# p0b-002.net
KiCad netlist of a schematic drawn in EAGLE
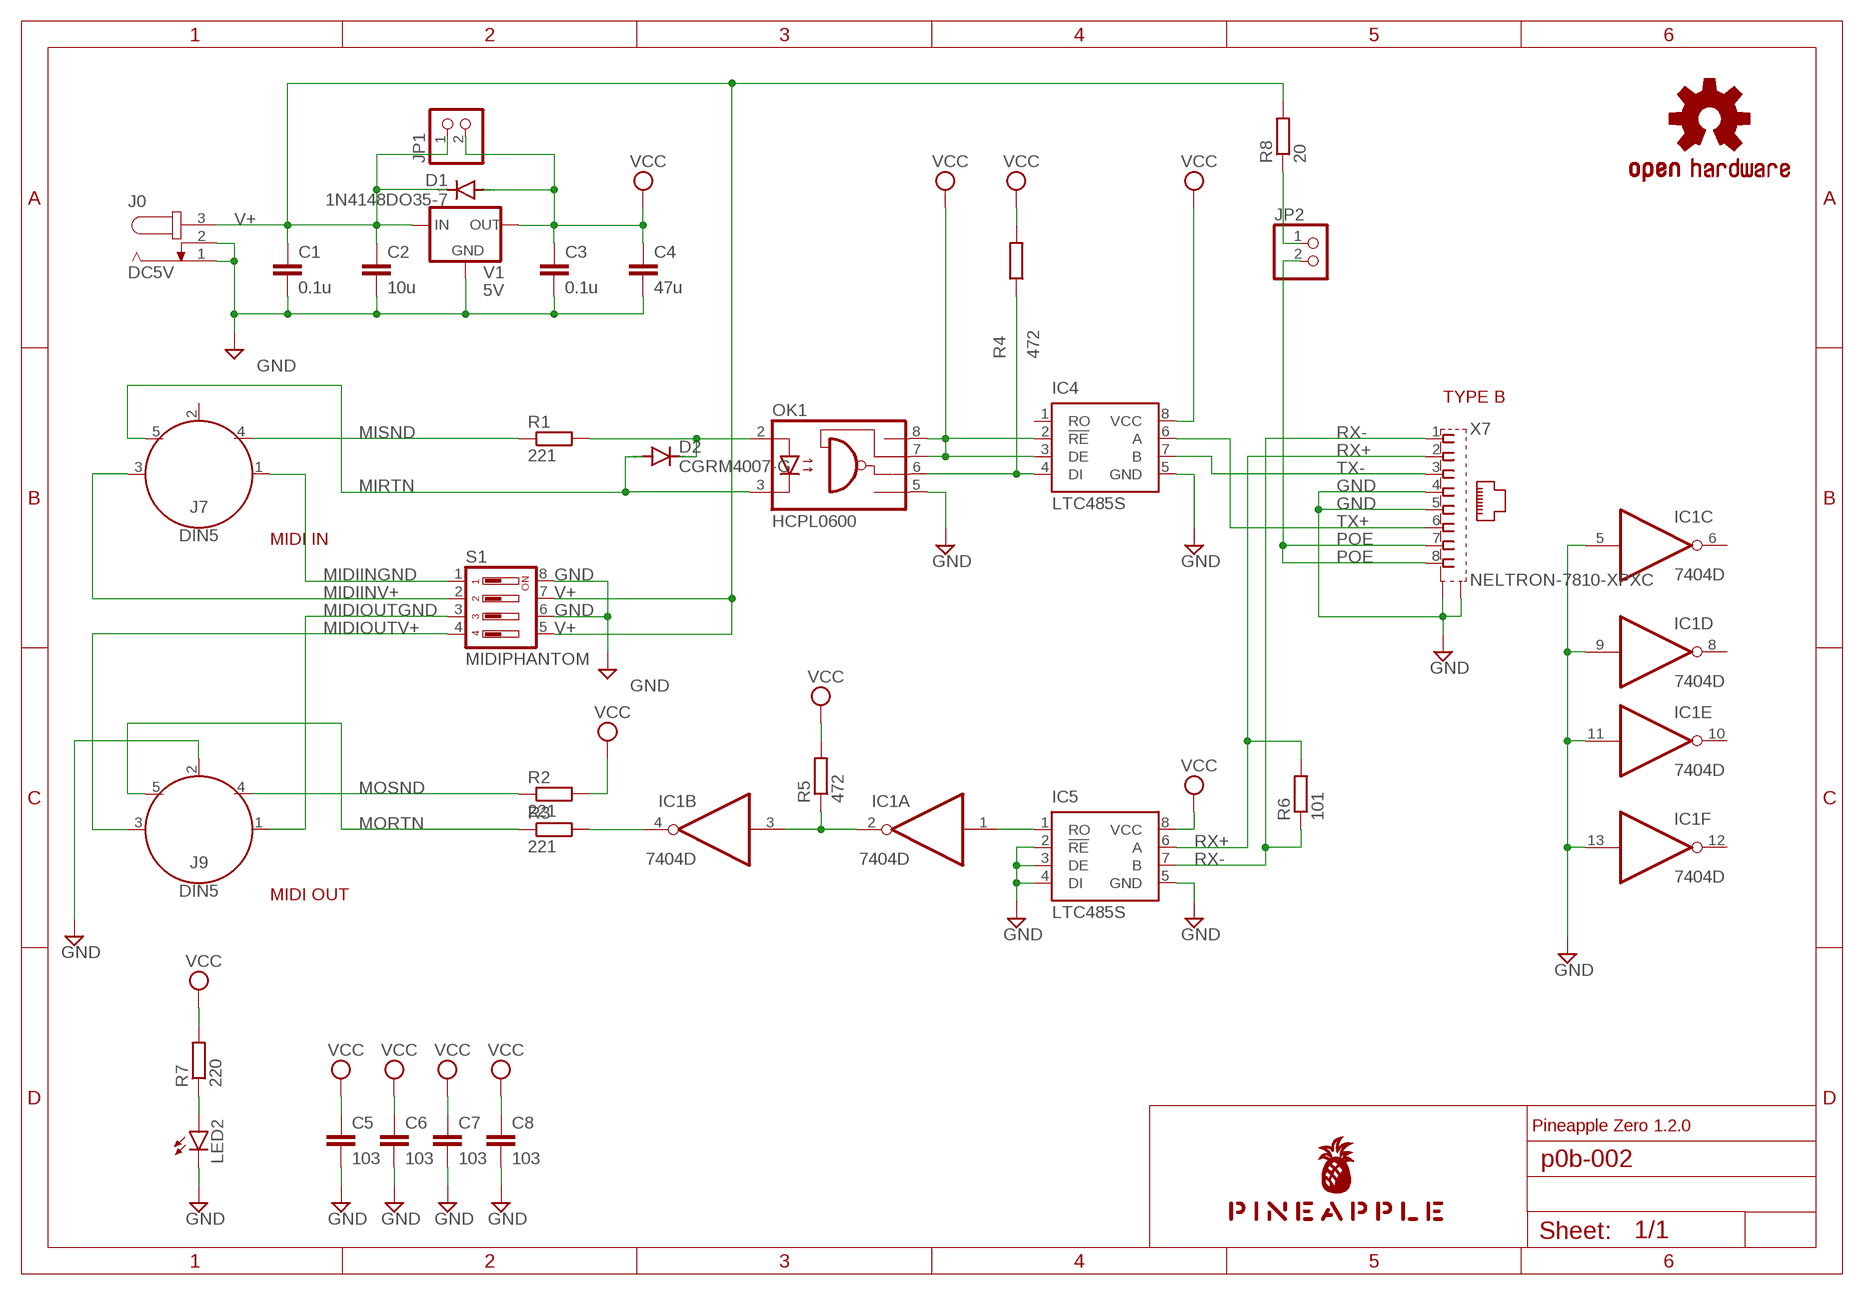
[diagram p0: schematic, sheet 1]

(export (version "E")
  (design (tool "Eeschema 10.0.6"))
  (components
    (comp (ref "C1")
      (value "0.1u")
      (footprint "eagle-import:C025-025X050")
      (libsource (lib "eagle-import") (part "C-EU025-025X050"))
    )
    (comp (ref "C2")
      (value "10u")
      (footprint "eagle-import:C025-030X050")
      (libsource (lib "eagle-import") (part "C-EU025-030X050"))
    )
    (comp (ref "C3")
      (value "0.1u")
      (footprint "eagle-import:C025-025X050")
      (libsource (lib "eagle-import") (part "C-EU025-025X050"))
    )
    (comp (ref "C4")
      (value "47u")
      (footprint "eagle-import:C025-050X050")
      (libsource (lib "eagle-import") (part "C-EU025-050X050"))
    )
    (comp (ref "C5")
      (value "103")
      (footprint "eagle-import:C1206")
      (libsource (lib "eagle-import") (part "C-EUC1206"))
    )
    (comp (ref "C6")
      (value "103")
      (footprint "eagle-import:C1206")
      (libsource (lib "eagle-import") (part "C-EUC1206"))
    )
    (comp (ref "C7")
      (value "103")
      (footprint "eagle-import:C1206")
      (libsource (lib "eagle-import") (part "C-EUC1206"))
    )
    (comp (ref "C8")
      (value "103")
      (footprint "eagle-import:C1206")
      (libsource (lib "eagle-import") (part "C-EUC1206"))
    )
    (comp (ref "D1")
      (value "1N4148DO35-7")
      (footprint "eagle-import:DO35-7")
      (libsource (lib "eagle-import") (part "1N4148DO35-7"))
    )
    (comp (ref "D2")
      (value "CGRM4007-G")
      (footprint "eagle-import:SOD-123_MINI-SMA")
      (libsource (lib "eagle-import") (part "CGRM400-G7"))
    )
    (comp (ref "IC1")
      (value "7404D")
      (footprint "eagle-import:SO14")
      (libsource (lib "eagle-import") (part "7404D"))
    )
    (comp (ref "IC4")
      (value "LTC485S")
      (footprint "eagle-import:SOIC8")
      (libsource (lib "eagle-import") (part "LTC485S"))
    )
    (comp (ref "IC5")
      (value "LTC485S")
      (footprint "eagle-import:SOIC8")
      (libsource (lib "eagle-import") (part "LTC485S"))
    )
    (comp (ref "J0")
      (value "DC5V")
      (footprint "eagle-import:SPC4077")
      (libsource (lib "eagle-import") (part "JACK-PLUG0"))
    )
    (comp (ref "J7")
      (value "DIN5")
      (footprint "eagle-import:DIN5-RA-PTH")
      (libsource (lib "eagle-import") (part "DIN5"))
    )
    (comp (ref "J9")
      (value "DIN5")
      (footprint "eagle-import:DIN5-RA-PTH")
      (libsource (lib "eagle-import") (part "DIN5"))
    )
    (comp (ref "JP1")
      (value "PINHD-1X2")
      (footprint "eagle-import:1X02")
      (libsource (lib "eagle-import") (part "PINHD-1X2"))
    )
    (comp (ref "JP2")
      (value "PINHD-1X2")
      (footprint "eagle-import:1X02")
      (libsource (lib "eagle-import") (part "PINHD-1X2"))
    )
    (comp (ref "LED2")
      (value "LEDCHIPLED_1206")
      (footprint "eagle-import:CHIPLED_1206")
      (libsource (lib "eagle-import") (part "LEDCHIPLED_1206"))
    )
    (comp (ref "LOGO1")
      (value "OSHW-LOGOS-COPPER")
      (footprint "eagle-import:OSHW-LOGO-S_COPPER")
      (libsource (lib "eagle-import") (part "OSHW-LOGOS-COPPER"))
    )
    (comp (ref "OK1")
      (value "HCPL0600")
      (footprint "eagle-import:SOIC08")
      (fields (field (name "MF") "AGILENT TECHNOLOGIES") (field (name "MPN") "HCPL-0600-000E"))
      (libsource (lib "eagle-import") (part "HCPL0600"))
    )
    (comp (ref "R1")
      (value "221")
      (footprint "eagle-import:M2012")
      (libsource (lib "eagle-import") (part "R-EU_M2012"))
    )
    (comp (ref "R2")
      (value "221")
      (footprint "eagle-import:M2012")
      (libsource (lib "eagle-import") (part "R-EU_M2012"))
    )
    (comp (ref "R3")
      (value "221")
      (footprint "eagle-import:M2012")
      (libsource (lib "eagle-import") (part "R-EU_M2012"))
    )
    (comp (ref "R4")
      (value "472")
      (footprint "eagle-import:M2012")
      (libsource (lib "eagle-import") (part "R-EU_M2012"))
    )
    (comp (ref "R5")
      (value "472")
      (footprint "eagle-import:M2012")
      (libsource (lib "eagle-import") (part "R-EU_M2012"))
    )
    (comp (ref "R6")
      (value "101")
      (footprint "eagle-import:M2012")
      (libsource (lib "eagle-import") (part "R-EU_M2012"))
    )
    (comp (ref "R7")
      (value "220")
      (footprint "eagle-import:M2012")
      (libsource (lib "eagle-import") (part "R-EU_M2012"))
    )
    (comp (ref "R8")
      (value "20")
      (footprint "eagle-import:M2012")
      (libsource (lib "eagle-import") (part "R-EU_M2012"))
    )
    (comp (ref "S1")
      (value "MIDIPHANTOM")
      (footprint "eagle-import:DIP04YL")
      (libsource (lib "eagle-import") (part "DIP04YL"))
    )
    (comp (ref "U$1")
      (value "PINEAPPLE450")
      (footprint "eagle-import:PINEAPPLE450")
      (libsource (lib "eagle-import") (part "PINEAPPLE450"))
    )
    (comp (ref "V1")
      (value "5V")
      (footprint "eagle-import:78XXS")
      (libsource (lib "eagle-import") (part "78XXS"))
    )
    (comp (ref "X7")
      (value "NELTRON-7810-XPXC")
      (footprint "eagle-import:NELTRON-7810-XPXC-FOOTPRINT")
      (libsource (lib "eagle-import") (part "NELTRON-7810-XPXC"))
    )
  )
  (nets
    (net (code "1") (name "/MIDIINGND") (class "Default")
      (node (ref "J7") (pin "1") (pinfunction "1_1") (pintype "bidirectional"))
      (node (ref "S1") (pin "1") (pinfunction "1_1") (pintype "passive"))
    )
    (net (code "2") (name "/MIDIINV+") (class "Default")
      (node (ref "J7") (pin "3") (pinfunction "3_3") (pintype "bidirectional"))
      (node (ref "S1") (pin "2") (pinfunction "2_2") (pintype "passive"))
    )
    (net (code "3") (name "/MIDIOUTGND") (class "Default")
      (node (ref "J9") (pin "1") (pinfunction "1_1") (pintype "bidirectional"))
      (node (ref "S1") (pin "3") (pinfunction "3_3") (pintype "passive"))
    )
    (net (code "4") (name "/MIDIOUTV+") (class "Default")
      (node (ref "J9") (pin "3") (pinfunction "3_3") (pintype "bidirectional"))
      (node (ref "S1") (pin "4") (pinfunction "4_4") (pintype "passive"))
    )
    (net (code "5") (name "/MIRTN") (class "Default")
      (node (ref "D2") (pin "A") (pinfunction "A_A") (pintype "passive"))
      (node (ref "J7") (pin "5") (pinfunction "5_5") (pintype "bidirectional"))
      (node (ref "OK1") (pin "3") (pinfunction "C_3") (pintype "passive"))
    )
    (net (code "6") (name "/MISND") (class "Default")
      (node (ref "J7") (pin "4") (pinfunction "4_4") (pintype "bidirectional"))
      (node (ref "R1") (pin "1") (pinfunction "1_1") (pintype "passive"))
    )
    (net (code "7") (name "/MORTN") (class "Default")
      (node (ref "J9") (pin "5") (pinfunction "5_5") (pintype "bidirectional"))
      (node (ref "R3") (pin "1") (pinfunction "1_1") (pintype "passive"))
    )
    (net (code "8") (name "/MOSND") (class "Default")
      (node (ref "J9") (pin "4") (pinfunction "4_4") (pintype "bidirectional"))
      (node (ref "R2") (pin "1") (pinfunction "1_1") (pintype "passive"))
    )
    (net (code "9") (name "/POE") (class "Default")
      (node (ref "JP2") (pin "2") (pinfunction "2_2") (pintype "passive"))
      (node (ref "X7") (pin "7") (pinfunction "7_7") (pintype "passive"))
      (node (ref "X7") (pin "8") (pinfunction "8_8") (pintype "passive"))
    )
    (net (code "10") (name "/RX+") (class "Default")
      (node (ref "IC5") (pin "6") (pinfunction "A_6") (pintype "bidirectional"))
      (node (ref "R6") (pin "2") (pinfunction "2_2") (pintype "passive"))
      (node (ref "X7") (pin "2") (pinfunction "2_2") (pintype "passive"))
    )
    (net (code "11") (name "/RX-") (class "Default")
      (node (ref "IC5") (pin "7") (pinfunction "B_7") (pintype "bidirectional"))
      (node (ref "R6") (pin "1") (pinfunction "1_1") (pintype "passive"))
      (node (ref "X7") (pin "1") (pinfunction "1_1") (pintype "passive"))
    )
    (net (code "12") (name "/TX+") (class "Default")
      (node (ref "IC4") (pin "6") (pinfunction "A_6") (pintype "bidirectional"))
      (node (ref "X7") (pin "6") (pinfunction "6_6") (pintype "passive"))
    )
    (net (code "13") (name "/TX-") (class "Default")
      (node (ref "IC4") (pin "7") (pinfunction "B_7") (pintype "bidirectional"))
      (node (ref "X7") (pin "3") (pinfunction "3_3") (pintype "passive"))
    )
    (net (code "14") (name "/V+") (class "Default")
      (node (ref "C1") (pin "1") (pinfunction "1_1") (pintype "passive"))
      (node (ref "C2") (pin "1") (pinfunction "1_1") (pintype "passive"))
      (node (ref "D1") (pin "C") (pinfunction "C_C") (pintype "passive"))
      (node (ref "J0") (pin "3") (pinfunction "3_3") (pintype "passive"))
      (node (ref "JP1") (pin "1") (pinfunction "1_1") (pintype "passive"))
      (node (ref "R8") (pin "2") (pinfunction "2_2") (pintype "passive"))
      (node (ref "S1") (pin "5") (pinfunction "5_5") (pintype "passive"))
      (node (ref "S1") (pin "7") (pinfunction "7_7") (pintype "passive"))
      (node (ref "V1") (pin "IN") (pinfunction "IN_IN") (pintype "input"))
    )
    (net (code "15") (name "GND") (class "Default")
      (node (ref "C1") (pin "2") (pinfunction "2_2") (pintype "passive"))
      (node (ref "C2") (pin "2") (pinfunction "2_2") (pintype "passive"))
      (node (ref "C3") (pin "2") (pinfunction "2_2") (pintype "passive"))
      (node (ref "C4") (pin "2") (pinfunction "2_2") (pintype "passive"))
      (node (ref "C5") (pin "2") (pinfunction "2_2") (pintype "passive"))
      (node (ref "C6") (pin "2") (pinfunction "2_2") (pintype "passive"))
      (node (ref "C7") (pin "2") (pinfunction "2_2") (pintype "passive"))
      (node (ref "C8") (pin "2") (pinfunction "2_2") (pintype "passive"))
      (node (ref "IC1") (pin "11") (pinfunction "I_11") (pintype "input"))
      (node (ref "IC1") (pin "13") (pinfunction "I_13") (pintype "input"))
      (node (ref "IC1") (pin "5") (pinfunction "I_5") (pintype "input"))
      (node (ref "IC1") (pin "9") (pinfunction "I_9") (pintype "input"))
      (node (ref "IC4") (pin "5") (pinfunction "GND_5") (pintype "input"))
      (node (ref "IC5") (pin "2") (pinfunction "~{RE}_2") (pintype "input"))
      (node (ref "IC5") (pin "3") (pinfunction "DE_3") (pintype "input"))
      (node (ref "IC5") (pin "4") (pinfunction "DI_4") (pintype "input"))
      (node (ref "IC5") (pin "5") (pinfunction "GND_5") (pintype "input"))
      (node (ref "J0") (pin "1") (pinfunction "1_1") (pintype "passive"))
      (node (ref "J0") (pin "2") (pinfunction "2_2") (pintype "passive"))
      (node (ref "J9") (pin "2") (pinfunction "2_2") (pintype "bidirectional"))
      (node (ref "LED2") (pin "C") (pinfunction "C_C") (pintype "passive"))
      (node (ref "OK1") (pin "5") (pinfunction "GND_5") (pintype "passive"))
      (node (ref "S1") (pin "6") (pinfunction "6_6") (pintype "passive"))
      (node (ref "S1") (pin "8") (pinfunction "8_8") (pintype "passive"))
      (node (ref "V1") (pin "GND") (pinfunction "GND_GND") (pintype "input"))
      (node (ref "X7") (pin "4") (pinfunction "4_4") (pintype "passive"))
      (node (ref "X7") (pin "5") (pinfunction "5_5") (pintype "passive"))
      (node (ref "X7") (pin "S1") (pinfunction "S1_S1") (pintype "passive"))
      (node (ref "X7") (pin "S2") (pinfunction "S2_S2") (pintype "passive"))
    )
    (net (code "16") (name "Net-(IC1A-I)") (class "Default")
      (node (ref "IC1") (pin "1") (pinfunction "I_1") (pintype "input"))
      (node (ref "IC5") (pin "1") (pinfunction "RO_1") (pintype "output"))
    )
    (net (code "17") (name "Net-(IC1A-O)") (class "Default")
      (node (ref "IC1") (pin "2") (pinfunction "O_2") (pintype "output"))
      (node (ref "IC1") (pin "3") (pinfunction "I_3") (pintype "input"))
      (node (ref "R5") (pin "1") (pinfunction "1_1") (pintype "passive"))
    )
    (net (code "18") (name "Net-(IC1B-O)") (class "Default")
      (node (ref "IC1") (pin "4") (pinfunction "O_4") (pintype "output"))
      (node (ref "R3") (pin "2") (pinfunction "2_2") (pintype "passive"))
    )
    (net (code "19") (name "Net-(IC4-DI)") (class "Default")
      (node (ref "IC4") (pin "4") (pinfunction "DI_4") (pintype "input"))
      (node (ref "OK1") (pin "6") (pinfunction "VO_6") (pintype "passive"))
      (node (ref "R4") (pin "1") (pinfunction "1_1") (pintype "passive"))
    )
    (net (code "20") (name "Net-(JP2-Pad1)") (class "Default")
      (node (ref "JP2") (pin "1") (pinfunction "1_1") (pintype "passive"))
      (node (ref "R8") (pin "1") (pinfunction "1_1") (pintype "passive"))
    )
    (net (code "21") (name "Net-(LED2-PadA)") (class "Default")
      (node (ref "LED2") (pin "A") (pinfunction "A_A") (pintype "passive"))
      (node (ref "R7") (pin "1") (pinfunction "1_1") (pintype "passive"))
    )
    (net (code "22") (name "Net-(OK1-A)") (class "Default")
      (node (ref "D2") (pin "C") (pinfunction "C_C") (pintype "passive"))
      (node (ref "OK1") (pin "2") (pinfunction "A_2") (pintype "passive"))
      (node (ref "R1") (pin "2") (pinfunction "2_2") (pintype "passive"))
    )
    (net (code "23") (name "VCC") (class "Default")
      (node (ref "C3") (pin "1") (pinfunction "1_1") (pintype "passive"))
      (node (ref "C4") (pin "1") (pinfunction "1_1") (pintype "passive"))
      (node (ref "C5") (pin "1") (pinfunction "1_1") (pintype "passive"))
      (node (ref "C6") (pin "1") (pinfunction "1_1") (pintype "passive"))
      (node (ref "C7") (pin "1") (pinfunction "1_1") (pintype "passive"))
      (node (ref "C8") (pin "1") (pinfunction "1_1") (pintype "passive"))
      (node (ref "D1") (pin "A") (pinfunction "A_A") (pintype "passive"))
      (node (ref "IC4") (pin "2") (pinfunction "~{RE}_2") (pintype "input"))
      (node (ref "IC4") (pin "3") (pinfunction "DE_3") (pintype "input"))
      (node (ref "IC4") (pin "8") (pinfunction "VCC_8") (pintype "input"))
      (node (ref "IC5") (pin "8") (pinfunction "VCC_8") (pintype "input"))
      (node (ref "JP1") (pin "2") (pinfunction "2_2") (pintype "passive"))
      (node (ref "OK1") (pin "7") (pinfunction "VE_7") (pintype "passive"))
      (node (ref "OK1") (pin "8") (pinfunction "VCC_8") (pintype "passive"))
      (node (ref "R2") (pin "2") (pinfunction "2_2") (pintype "passive"))
      (node (ref "R4") (pin "2") (pinfunction "2_2") (pintype "passive"))
      (node (ref "R5") (pin "2") (pinfunction "2_2") (pintype "passive"))
      (node (ref "R7") (pin "2") (pinfunction "2_2") (pintype "passive"))
      (node (ref "V1") (pin "OUT") (pinfunction "OUT_OUT") (pintype "passive"))
    )
    (net (code "24") (name "unconnected-(IC1C-O-Pad6)") (class "Default")
      (node (ref "IC1") (pin "6") (pinfunction "O_6") (pintype "output"))
    )
    (net (code "25") (name "unconnected-(IC1D-O-Pad8)") (class "Default")
      (node (ref "IC1") (pin "8") (pinfunction "O_8") (pintype "output"))
    )
    (net (code "26") (name "unconnected-(IC1E-O-Pad10)") (class "Default")
      (node (ref "IC1") (pin "10") (pinfunction "O_10") (pintype "output"))
    )
    (net (code "27") (name "unconnected-(IC1F-O-Pad12)") (class "Default")
      (node (ref "IC1") (pin "12") (pinfunction "O_12") (pintype "output"))
    )
    (net (code "28") (name "unconnected-(IC4-RO-Pad1)") (class "Default")
      (node (ref "IC4") (pin "1") (pinfunction "RO_1") (pintype "output"))
    )
    (net (code "29") (name "unconnected-(J7-Pad2)") (class "Default")
      (node (ref "J7") (pin "2") (pinfunction "2_2") (pintype "bidirectional"))
    )
  )
)
